# Easyeda_xl6007.net
KiCad netlist of a schematic drawn in Altium Designer
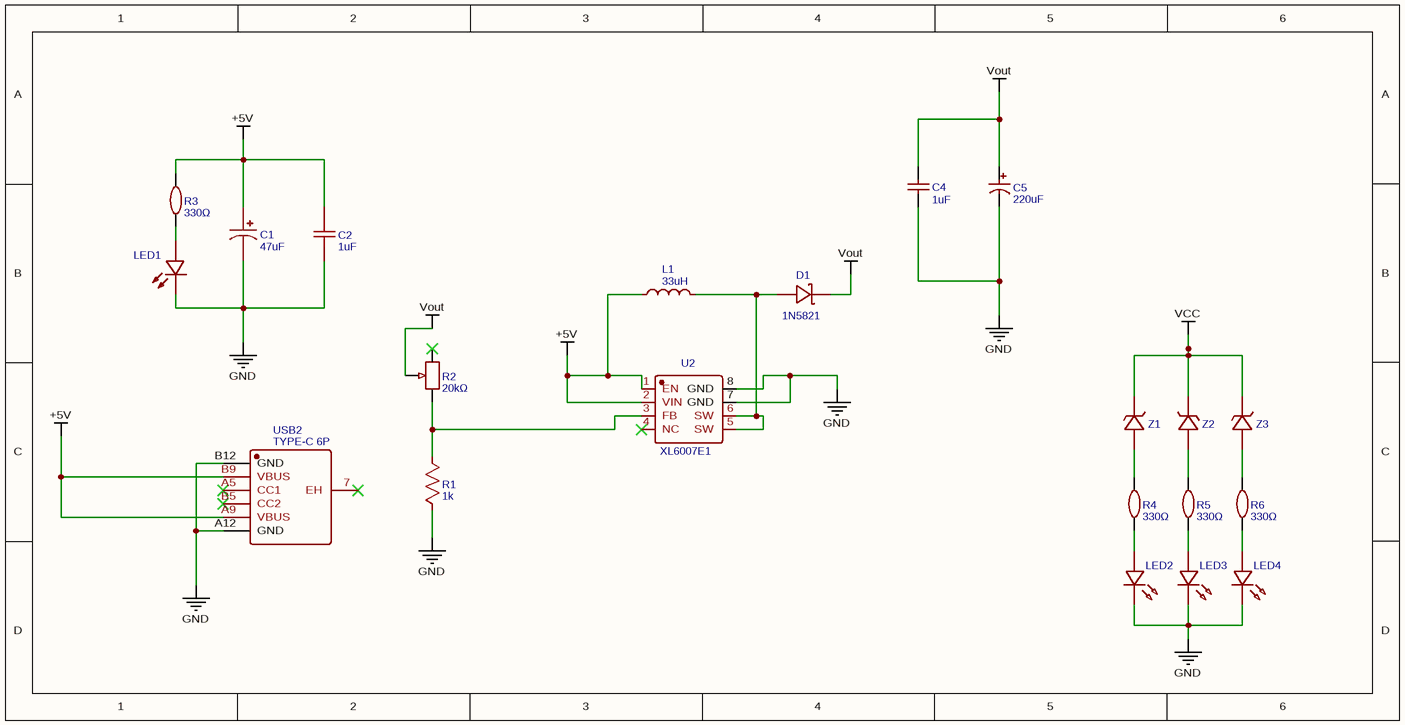
[diagram p0: Easyeda xl6007.schdoc]

(export (version "E")
  (design (tool "Eeschema 10.0.6"))
  (components
    (comp (ref "C1")
      (value "47uF")
      (footprint "CAP-TH_BD6.3-P2.5-D0.5")
      (fields
        (field (name "MANUFACTURER") "HRK(鸿瑞凯电子)")
        (field (name "MANUFACTURER PART") "50V47uF CD288")
        (field (name "CONTRIBUTOR") "lcsc")
      )
      (libsource (lib "altium-import") (part "root_3_47uF_"))
    )
    (comp (ref "C2")
      (value "1uF")
      (footprint "C0402")
      (fields
        (field (name "MANUFACTURER") "Walsin(华新科)")
        (field (name "MANUFACTURER PART") "0402X105K100CT")
        (field (name "CONTRIBUTOR") "LCSC")
      )
      (libsource (lib "") (part "root_1_1uF__1"))
    )
    (comp (ref "C4")
      (value "1uF")
      (footprint "C0805")
      (fields
        (field (name "MANUFACTURER PART") "CL21B105KBFNNNE")
        (field (name "MANUFACTURER") "SAMSUNG(三星)")
      )
      (libsource (lib "altium-import") (part "root_1_1uF_"))
    )
    (comp (ref "C5")
      (value "220uF")
      (footprint "CAP-TH_BD8.0-P3.50-D0.6-FD")
      (fields (field (name "MANUFACTURER") "AISHI(艾华集团)") (field (name "MANUFACTURER PART") "ERE1VM221F12OT"))
      (libsource (lib "altium-import") (part "root_3_220uF_"))
    )
    (comp (ref "D1")
      (value "1N5821")
      (footprint "DO-201AD_BD5.3-L8.4-P12.50-D1.4-RD")
      (fields (field (name "MANUFACTURER") "onsemi(安森美)") (field (name "MANUFACTURER PART") "1N5821RLG"))
      (libsource (lib "altium-import") (part "root_2_1N5821_"))
    )
    (comp (ref "L1")
      (value "33uH")
      (footprint "IND-SMD_L11.5-W10.5_MJC-1040T")
      (fields
        (field (name "MANUFACTURER") "FC(方成)")
        (field (name "MANUFACTURER PART") "FCH1040-330M")
        (field (name "CONTRIBUTOR") "lcsc")
      )
      (libsource (lib "altium-import") (part "root_0_33uH_"))
    )
    (comp (ref "LED1")
      (value "KT-0603R")
      (footprint "LED0603-RD")
      (fields (field (name "MANUFACTURER") "KENTO"))
      (libsource (lib "altium-import") (part "root_1_KT-0603R_"))
    )
    (comp (ref "LED2")
      (value "LED-0603_G")
      (footprint "LED0603_GREEN")
      (fields
        (field (name "MANUFACTURER") "EVERLIGHT(台湾亿光)")
        (field (name "MANUFACTURER PART") "19-217/GHC-YR1S2/3T")
        (field (name "CONTRIBUTOR") "LCEDA_Lib")
      )
      (libsource (lib "altium-import") (part "root_3_LED-0603_G_"))
    )
    (comp (ref "LED3")
      (value "R2")
      (footprint "LED0603_RED")
      (fields
        (field (name "MANUFACTURER") "EVERLIGHT(台湾亿光)")
        (field (name "MANUFACTURER PART") "19-217/R6C-AL1M2VY/3T")
        (field (name "CONTRIBUTOR") "LCEDA_01")
      )
      (libsource (lib "altium-import") (part "root_3_R2_"))
    )
    (comp (ref "LED4")
      (value "LED-0603_B")
      (footprint "LED0603_BLUE")
      (fields
        (field (name "MANUFACTURER") "EVERLIGHT(台湾亿光)")
        (field (name "MANUFACTURER PART") "19-217/BHC-ZL1M2RY/3T")
        (field (name "CONTRIBUTOR") "LCEDA_01")
      )
      (libsource (lib "altium-import") (part "root_3_LED-0603_B_"))
    )
    (comp (ref "R1")
      (value "1k")
      (footprint "R_AXIAL-0.3")
      (fields (field (name "CONTRIBUTOR") "LCEDA_Lib"))
      (libsource (lib "altium-import") (part "root_1_1k_"))
    )
    (comp (ref "R2")
      (value "20kΩ")
      (footprint "RES-ADJ-TH_3P-L7.1-W6.9-P2.50-L_3362P")
      (fields
        (field (name "MANUFACTURER") "BOCHEN(博晨)")
        (field (name "MANUFACTURER PART") "3362P-1-203")
        (field (name "CONTRIBUTOR") "LCSC")
      )
      (libsource (lib "altium-import") (part "root_0_20kΩ_"))
    )
    (comp (ref "R3")
      (value "330Ω")
      (footprint "R0603")
      (fields
        (field (name "MANUFACTURER") "UNI-ROYAL(厚声)")
        (field (name "MANUFACTURER PART") "0603WAF3300T5E")
      )
      (libsource (lib "altium-import") (part "root_1_330Ω_"))
    )
    (comp (ref "R4")
      (value "330Ω")
      (footprint "R0603")
      (fields
        (field (name "MANUFACTURER") "UNI-ROYAL(厚声)")
        (field (name "MANUFACTURER PART") "0603WAF3300T5E")
      )
      (libsource (lib "altium-import") (part "root_1_330Ω_"))
    )
    (comp (ref "R5")
      (value "330Ω")
      (footprint "R0603")
      (fields
        (field (name "MANUFACTURER") "UNI-ROYAL(厚声)")
        (field (name "MANUFACTURER PART") "0603WAF3300T5E")
      )
      (libsource (lib "altium-import") (part "root_1_330Ω_"))
    )
    (comp (ref "R6")
      (value "330Ω")
      (footprint "R0603")
      (fields
        (field (name "MANUFACTURER") "UNI-ROYAL(厚声)")
        (field (name "MANUFACTURER PART") "0603WAF3300T5E")
      )
      (libsource (lib "altium-import") (part "root_1_330Ω_"))
    )
    (comp (ref "U2")
      (value "XL6007E1")
      (footprint "SOIC-8_L4.9-W3.8-P1.27-LS6.0-BL")
      (fields (field (name "MANUFACTURER") "XLSEMI(芯龙)") (field (name "CONTRIBUTOR") "lcsc"))
      (libsource (lib "altium-import") (part "root_0_XL6007E1_"))
    )
    (comp (ref "USB2")
      (value "TYPE-C 6P")
      (footprint "TYPE-C-SMD_TYPE-C-6P")
      (fields (field (name "MANUFACTURER") "SHOU HAN(首韩)") (field (name "CONTRIBUTOR") "LCSC"))
      (libsource (lib "altium-import") (part "root_0_TYPE-C 6P_"))
    )
    (comp (ref "Z1")
      (value "Z1")
      (footprint "SOD-523_L1.2-W0.8-LS1.6-RD")
      (fields
        (field (name "MANUFACTURER") "CJ(江苏长电/长晶)")
        (field (name "MANUFACTURER PART") "BZX584C8V2")
        (field (name "CONTRIBUTOR") "lcsc")
      )
      (libsource (lib "altium-import") (part "root_3_Z1_"))
    )
    (comp (ref "Z2")
      (value "Z2")
      (footprint "SOD-523_L1.2-W0.8-LS1.6-FD")
      (fields
        (field (name "MANUFACTURER") "宏迦橙")
        (field (name "MANUFACTURER PART") "BZX584C15")
        (field (name "CONTRIBUTOR") "lcsc")
      )
      (libsource (lib "altium-import") (part "root_1_Z2_"))
    )
    (comp (ref "Z3")
      (value "Z3")
      (footprint "SOD-523_L1.2-W0.8-LS1.6-RD")
      (fields (field (name "MANUFACTURER PART") "BZX584C20-TP") (field (name "CONTRIBUTOR") "LCSC"))
      (libsource (lib "altium-import") (part "root_3_Z3_"))
    )
  )
  (nets
    (net (code "1") (name "+5V") (class "Default")
      (node (ref "C1") (pin "1") (pinfunction "1_1") (pintype "passive"))
      (node (ref "C2") (pin "1") (pinfunction "1_1") (pintype "passive"))
      (node (ref "L1") (pin "1") (pinfunction "1_1") (pintype "passive"))
      (node (ref "R3") (pin "2") (pinfunction "2_2") (pintype "passive"))
      (node (ref "U2") (pin "1") (pinfunction "EN_1") (pintype "passive"))
      (node (ref "U2") (pin "2") (pinfunction "VIN_2") (pintype "passive"))
      (node (ref "USB2") (pin "A9") (pinfunction "VBUS_A9") (pintype "passive"))
      (node (ref "USB2") (pin "B9") (pinfunction "VBUS_B9") (pintype "passive"))
    )
    (net (code "2") (name "GND") (class "Default")
      (node (ref "C1") (pin "2") (pinfunction "2_2") (pintype "passive"))
      (node (ref "C2") (pin "2") (pinfunction "2_2") (pintype "passive"))
      (node (ref "C4") (pin "1") (pinfunction "1_1") (pintype "passive"))
      (node (ref "C5") (pin "2") (pinfunction "2_2") (pintype "passive"))
      (node (ref "LED1") (pin "1") (pinfunction "K_1") (pintype "passive"))
      (node (ref "LED2") (pin "2") (pinfunction "2_2") (pintype "passive"))
      (node (ref "LED3") (pin "2") (pinfunction "2_2") (pintype "passive"))
      (node (ref "LED4") (pin "2") (pinfunction "2_2") (pintype "passive"))
      (node (ref "R1") (pin "1") (pinfunction "1_1") (pintype "passive"))
      (node (ref "U2") (pin "7") (pinfunction "GND_7") (pintype "passive"))
      (node (ref "U2") (pin "8") (pinfunction "GND_8") (pintype "passive"))
      (node (ref "USB2") (pin "A12") (pinfunction "GND_A12") (pintype "passive"))
      (node (ref "USB2") (pin "B12") (pinfunction "GND_B12") (pintype "passive"))
    )
    (net (code "3") (name "Net-(D1-A)") (class "Default")
      (node (ref "D1") (pin "2") (pinfunction "A_2") (pintype "passive"))
      (node (ref "L1") (pin "2") (pinfunction "2_2") (pintype "passive"))
      (node (ref "U2") (pin "5") (pinfunction "SW_5") (pintype "passive"))
      (node (ref "U2") (pin "6") (pinfunction "SW_6") (pintype "passive"))
    )
    (net (code "4") (name "Net-(LED1-A)") (class "Default")
      (node (ref "LED1") (pin "2") (pinfunction "A_2") (pintype "passive"))
      (node (ref "R3") (pin "1") (pinfunction "1_1") (pintype "passive"))
    )
    (net (code "5") (name "Net-(LED2-Pad1)") (class "Default")
      (node (ref "LED2") (pin "1") (pinfunction "1_1") (pintype "passive"))
      (node (ref "R4") (pin "1") (pinfunction "1_1") (pintype "passive"))
    )
    (net (code "6") (name "Net-(LED3-Pad1)") (class "Default")
      (node (ref "LED3") (pin "1") (pinfunction "1_1") (pintype "passive"))
      (node (ref "R5") (pin "1") (pinfunction "1_1") (pintype "passive"))
    )
    (net (code "7") (name "Net-(LED4-Pad1)") (class "Default")
      (node (ref "LED4") (pin "1") (pinfunction "1_1") (pintype "passive"))
      (node (ref "R6") (pin "1") (pinfunction "1_1") (pintype "passive"))
    )
    (net (code "8") (name "Net-(U2-FB)") (class "Default")
      (node (ref "R1") (pin "2") (pinfunction "2_2") (pintype "passive"))
      (node (ref "R2") (pin "1") (pinfunction "1_1") (pintype "passive"))
      (node (ref "U2") (pin "3") (pinfunction "FB_3") (pintype "passive"))
    )
    (net (code "9") (name "Net-(Z1-A)") (class "Default")
      (node (ref "R4") (pin "2") (pinfunction "2_2") (pintype "passive"))
      (node (ref "Z1") (pin "2") (pinfunction "A_2") (pintype "passive"))
    )
    (net (code "10") (name "Net-(Z2-A)") (class "Default")
      (node (ref "R5") (pin "2") (pinfunction "2_2") (pintype "passive"))
      (node (ref "Z2") (pin "1") (pinfunction "A_1") (pintype "passive"))
    )
    (net (code "11") (name "Net-(Z3-A)") (class "Default")
      (node (ref "R6") (pin "2") (pinfunction "2_2") (pintype "passive"))
      (node (ref "Z3") (pin "2") (pinfunction "A_2") (pintype "passive"))
    )
    (net (code "12") (name "VCC") (class "Default")
      (node (ref "Z1") (pin "1") (pinfunction "K_1") (pintype "passive"))
      (node (ref "Z2") (pin "2") (pinfunction "K_2") (pintype "passive"))
      (node (ref "Z3") (pin "1") (pinfunction "K_1") (pintype "passive"))
    )
    (net (code "13") (name "Vout") (class "Default")
      (node (ref "C4") (pin "2") (pinfunction "2_2") (pintype "passive"))
      (node (ref "C5") (pin "1") (pinfunction "1_1") (pintype "passive"))
      (node (ref "D1") (pin "1") (pinfunction "C_1") (pintype "passive"))
      (node (ref "R2") (pin "2") (pinfunction "2_2") (pintype "passive"))
    )
    (net (code "14") (name "unconnected-(R2-Pad3)") (class "Default")
      (node (ref "R2") (pin "3") (pinfunction "3_3") (pintype "passive+no_connect"))
    )
    (net (code "15") (name "unconnected-(U2-NC-Pad4)") (class "Default")
      (node (ref "U2") (pin "4") (pinfunction "NC_4") (pintype "passive+no_connect"))
    )
    (net (code "16") (name "unconnected-(USB2-CC1-PadA5)") (class "Default")
      (node (ref "USB2") (pin "A5") (pinfunction "CC1_A5") (pintype "passive+no_connect"))
    )
    (net (code "17") (name "unconnected-(USB2-CC2-PadB5)") (class "Default")
      (node (ref "USB2") (pin "B5") (pinfunction "CC2_B5") (pintype "passive+no_connect"))
    )
    (net (code "18") (name "unconnected-(USB2-EH-Pad7)") (class "Default")
      (node (ref "USB2") (pin "7") (pinfunction "EH_7") (pintype "passive+no_connect"))
    )
  )
)
